# BD0006_1_digit.net
KiCad netlist of a schematic drawn in EAGLE
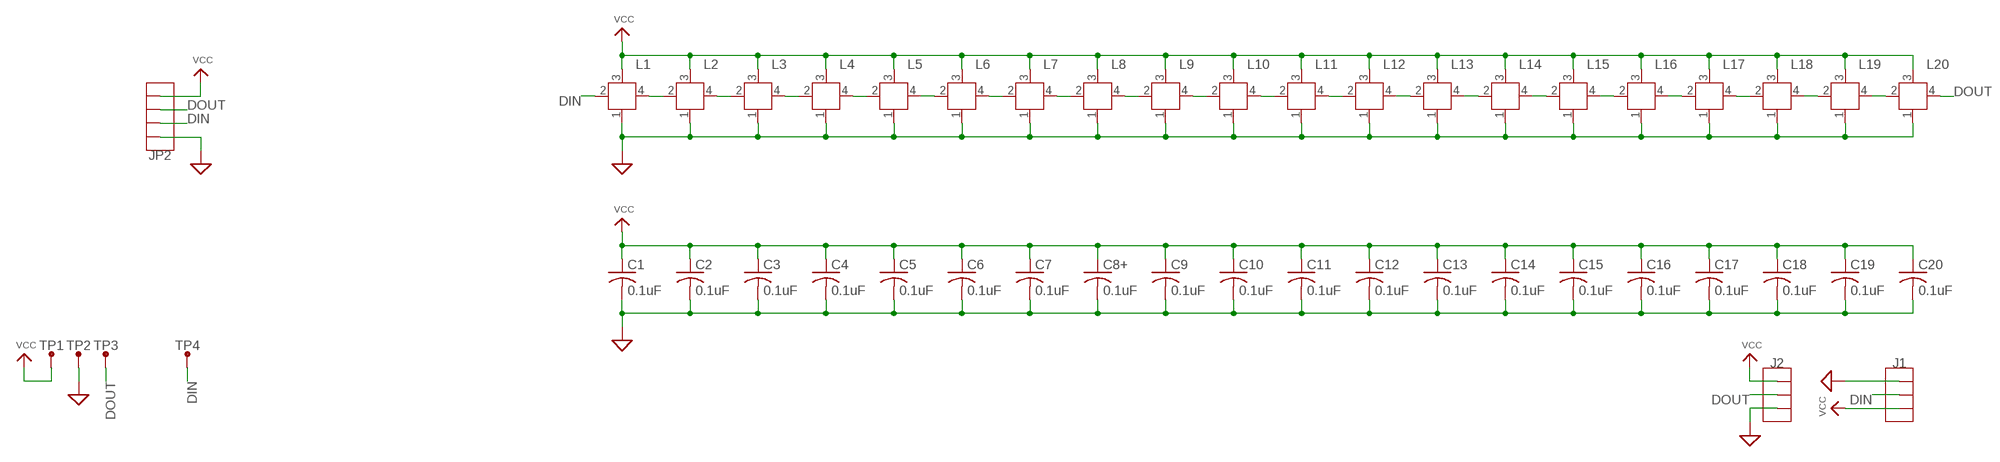
[diagram p0: schematic, sheet 1]

(export (version "E")
  (design (tool "Eeschema 10.0.6"))
  (components
    (comp (ref "C1")
      (value "0.1uF")
      (footprint "eagle-import:C0402")
      (libsource (lib "eagle-import") (part "C-USC0402"))
    )
    (comp (ref "C2")
      (value "0.1uF")
      (footprint "eagle-import:C0402")
      (libsource (lib "eagle-import") (part "C-USC0402"))
    )
    (comp (ref "C3")
      (value "0.1uF")
      (footprint "eagle-import:C0402")
      (libsource (lib "eagle-import") (part "C-USC0402"))
    )
    (comp (ref "C4")
      (value "0.1uF")
      (footprint "eagle-import:C0402")
      (libsource (lib "eagle-import") (part "C-USC0402"))
    )
    (comp (ref "C5")
      (value "0.1uF")
      (footprint "eagle-import:C0402")
      (libsource (lib "eagle-import") (part "C-USC0402"))
    )
    (comp (ref "C6")
      (value "0.1uF")
      (footprint "eagle-import:C0402")
      (libsource (lib "eagle-import") (part "C-USC0402"))
    )
    (comp (ref "C7")
      (value "0.1uF")
      (footprint "eagle-import:C0402")
      (libsource (lib "eagle-import") (part "C-USC0402"))
    )
    (comp (ref "C8+")
      (value "0.1uF")
      (footprint "eagle-import:C0402")
      (libsource (lib "eagle-import") (part "C-USC0402"))
    )
    (comp (ref "C9")
      (value "0.1uF")
      (footprint "eagle-import:C0402")
      (libsource (lib "eagle-import") (part "C-USC0402"))
    )
    (comp (ref "C10")
      (value "0.1uF")
      (footprint "eagle-import:C0402")
      (libsource (lib "eagle-import") (part "C-USC0402"))
    )
    (comp (ref "C11")
      (value "0.1uF")
      (footprint "eagle-import:C0402")
      (libsource (lib "eagle-import") (part "C-USC0402"))
    )
    (comp (ref "C12")
      (value "0.1uF")
      (footprint "eagle-import:C0402")
      (libsource (lib "eagle-import") (part "C-USC0402"))
    )
    (comp (ref "C13")
      (value "0.1uF")
      (footprint "eagle-import:C0402")
      (libsource (lib "eagle-import") (part "C-USC0402"))
    )
    (comp (ref "C14")
      (value "0.1uF")
      (footprint "eagle-import:C0402")
      (libsource (lib "eagle-import") (part "C-USC0402"))
    )
    (comp (ref "C15")
      (value "0.1uF")
      (footprint "eagle-import:C0402")
      (libsource (lib "eagle-import") (part "C-USC0402"))
    )
    (comp (ref "C16")
      (value "0.1uF")
      (footprint "eagle-import:C0402")
      (libsource (lib "eagle-import") (part "C-USC0402"))
    )
    (comp (ref "C17")
      (value "0.1uF")
      (footprint "eagle-import:C0402")
      (libsource (lib "eagle-import") (part "C-USC0402"))
    )
    (comp (ref "C18")
      (value "0.1uF")
      (footprint "eagle-import:C0402")
      (libsource (lib "eagle-import") (part "C-USC0402"))
    )
    (comp (ref "C19")
      (value "0.1uF")
      (footprint "eagle-import:C0402")
      (libsource (lib "eagle-import") (part "C-USC0402"))
    )
    (comp (ref "C20")
      (value "0.1uF")
      (footprint "eagle-import:C0402")
      (libsource (lib "eagle-import") (part "C-USC0402"))
    )
    (comp (ref "J1")
      (value "HEADER_1X3MALE")
      (footprint "eagle-import:M3SMD")
      (libsource (lib "eagle-import") (part "HEADER_1X3MALE"))
    )
    (comp (ref "J2")
      (value "HEADER_1X3FEMALE")
      (footprint "eagle-import:F3SMD")
      (libsource (lib "eagle-import") (part "HEADER_1X3FEMALE"))
    )
    (comp (ref "JP2")
      (value "HEADER_1X4S")
      (footprint "eagle-import:1X04")
      (libsource (lib "eagle-import") (part "HEADER_1X4S"))
    )
    (comp (ref "L1")
      (value "WS2812B")
      (footprint "eagle-import:SK6812")
      (libsource (lib "eagle-import") (part "WS2812B"))
    )
    (comp (ref "L2")
      (value "WS2812B")
      (footprint "eagle-import:SK6812")
      (libsource (lib "eagle-import") (part "WS2812B"))
    )
    (comp (ref "L3")
      (value "WS2812B")
      (footprint "eagle-import:SK6812")
      (libsource (lib "eagle-import") (part "WS2812B"))
    )
    (comp (ref "L4")
      (value "WS2812B")
      (footprint "eagle-import:SK6812")
      (libsource (lib "eagle-import") (part "WS2812B"))
    )
    (comp (ref "L5")
      (value "WS2812B")
      (footprint "eagle-import:SK6812")
      (libsource (lib "eagle-import") (part "WS2812B"))
    )
    (comp (ref "L6")
      (value "WS2812B")
      (footprint "eagle-import:SK6812")
      (libsource (lib "eagle-import") (part "WS2812B"))
    )
    (comp (ref "L7")
      (value "WS2812B")
      (footprint "eagle-import:SK6812")
      (libsource (lib "eagle-import") (part "WS2812B"))
    )
    (comp (ref "L8")
      (value "WS2812B")
      (footprint "eagle-import:SK6812")
      (libsource (lib "eagle-import") (part "WS2812B"))
    )
    (comp (ref "L9")
      (value "WS2812B")
      (footprint "eagle-import:SK6812")
      (libsource (lib "eagle-import") (part "WS2812B"))
    )
    (comp (ref "L10")
      (value "WS2812B")
      (footprint "eagle-import:SK6812")
      (libsource (lib "eagle-import") (part "WS2812B"))
    )
    (comp (ref "L11")
      (value "WS2812B")
      (footprint "eagle-import:SK6812")
      (libsource (lib "eagle-import") (part "WS2812B"))
    )
    (comp (ref "L12")
      (value "WS2812B")
      (footprint "eagle-import:SK6812")
      (libsource (lib "eagle-import") (part "WS2812B"))
    )
    (comp (ref "L13")
      (value "WS2812B")
      (footprint "eagle-import:SK6812")
      (libsource (lib "eagle-import") (part "WS2812B"))
    )
    (comp (ref "L14")
      (value "WS2812B")
      (footprint "eagle-import:SK6812")
      (libsource (lib "eagle-import") (part "WS2812B"))
    )
    (comp (ref "L15")
      (value "WS2812B")
      (footprint "eagle-import:SK6812")
      (libsource (lib "eagle-import") (part "WS2812B"))
    )
    (comp (ref "L16")
      (value "WS2812B")
      (footprint "eagle-import:SK6812")
      (libsource (lib "eagle-import") (part "WS2812B"))
    )
    (comp (ref "L17")
      (value "WS2812B")
      (footprint "eagle-import:SK6812")
      (libsource (lib "eagle-import") (part "WS2812B"))
    )
    (comp (ref "L18")
      (value "WS2812B")
      (footprint "eagle-import:SK6812")
      (libsource (lib "eagle-import") (part "WS2812B"))
    )
    (comp (ref "L19")
      (value "WS2812B")
      (footprint "eagle-import:SK6812")
      (libsource (lib "eagle-import") (part "WS2812B"))
    )
    (comp (ref "L20")
      (value "WS2812B")
      (footprint "eagle-import:SK6812")
      (libsource (lib "eagle-import") (part "WS2812B"))
    )
    (comp (ref "TP1")
      (value "VCC")
      (footprint "eagle-import:TEST_POINT")
      (libsource (lib "eagle-import") (part "TEST_POINT"))
    )
    (comp (ref "TP2")
      (value "GND")
      (footprint "eagle-import:TEST_POINT")
      (libsource (lib "eagle-import") (part "TEST_POINT"))
    )
    (comp (ref "TP3")
      (value "DOUT")
      (footprint "eagle-import:TEST_POINT")
      (libsource (lib "eagle-import") (part "TEST_POINT"))
    )
    (comp (ref "TP4")
      (value "DIN")
      (footprint "eagle-import:TEST_POINT")
      (libsource (lib "eagle-import") (part "TEST_POINT"))
    )
  )
  (nets
    (net (code "1") (name "/DIN") (class "Default")
      (node (ref "J1") (pin "2") (pinfunction "P$2_2") (pintype "bidirectional"))
      (node (ref "JP2") (pin "2") (pinfunction "P$2_2") (pintype "bidirectional"))
      (node (ref "L1") (pin "2") (pinfunction "DIN_2") (pintype "bidirectional"))
      (node (ref "TP4") (pin "P$1") (pinfunction "P$1_P$1") (pintype "input"))
    )
    (net (code "2") (name "/DOUT") (class "Default")
      (node (ref "J2") (pin "2A") (pinfunction "P$2_2A") (pintype "bidirectional"))
      (node (ref "J2") (pin "2B") (pinfunction "P$2_2B") (pintype "bidirectional"))
      (node (ref "JP2") (pin "3") (pinfunction "P$3_3") (pintype "bidirectional"))
      (node (ref "L20") (pin "4") (pinfunction "DOUT_4") (pintype "bidirectional"))
      (node (ref "TP3") (pin "P$1") (pinfunction "P$1_P$1") (pintype "input"))
    )
    (net (code "3") (name "Net-(L1-DOUT)") (class "Default")
      (node (ref "L1") (pin "4") (pinfunction "DOUT_4") (pintype "bidirectional"))
      (node (ref "L2") (pin "2") (pinfunction "DIN_2") (pintype "bidirectional"))
    )
    (net (code "4") (name "Net-(L2-DOUT)") (class "Default")
      (node (ref "L2") (pin "4") (pinfunction "DOUT_4") (pintype "bidirectional"))
      (node (ref "L3") (pin "2") (pinfunction "DIN_2") (pintype "bidirectional"))
    )
    (net (code "5") (name "Net-(L3-DOUT)") (class "Default")
      (node (ref "L3") (pin "4") (pinfunction "DOUT_4") (pintype "bidirectional"))
      (node (ref "L4") (pin "2") (pinfunction "DIN_2") (pintype "bidirectional"))
    )
    (net (code "6") (name "Net-(L4-DOUT)") (class "Default")
      (node (ref "L4") (pin "4") (pinfunction "DOUT_4") (pintype "bidirectional"))
      (node (ref "L5") (pin "2") (pinfunction "DIN_2") (pintype "bidirectional"))
    )
    (net (code "7") (name "Net-(L5-DOUT)") (class "Default")
      (node (ref "L5") (pin "4") (pinfunction "DOUT_4") (pintype "bidirectional"))
      (node (ref "L6") (pin "2") (pinfunction "DIN_2") (pintype "bidirectional"))
    )
    (net (code "8") (name "Net-(L6-DOUT)") (class "Default")
      (node (ref "L6") (pin "4") (pinfunction "DOUT_4") (pintype "bidirectional"))
      (node (ref "L7") (pin "2") (pinfunction "DIN_2") (pintype "bidirectional"))
    )
    (net (code "9") (name "Net-(L7-DOUT)") (class "Default")
      (node (ref "L7") (pin "4") (pinfunction "DOUT_4") (pintype "bidirectional"))
      (node (ref "L8") (pin "2") (pinfunction "DIN_2") (pintype "bidirectional"))
    )
    (net (code "10") (name "Net-(L8-DOUT)") (class "Default")
      (node (ref "L8") (pin "4") (pinfunction "DOUT_4") (pintype "bidirectional"))
      (node (ref "L9") (pin "2") (pinfunction "DIN_2") (pintype "bidirectional"))
    )
    (net (code "11") (name "Net-(L10-DIN)") (class "Default")
      (node (ref "L10") (pin "2") (pinfunction "DIN_2") (pintype "bidirectional"))
      (node (ref "L9") (pin "4") (pinfunction "DOUT_4") (pintype "bidirectional"))
    )
    (net (code "12") (name "Net-(L10-DOUT)") (class "Default")
      (node (ref "L10") (pin "4") (pinfunction "DOUT_4") (pintype "bidirectional"))
      (node (ref "L11") (pin "2") (pinfunction "DIN_2") (pintype "bidirectional"))
    )
    (net (code "13") (name "Net-(L11-DOUT)") (class "Default")
      (node (ref "L11") (pin "4") (pinfunction "DOUT_4") (pintype "bidirectional"))
      (node (ref "L12") (pin "2") (pinfunction "DIN_2") (pintype "bidirectional"))
    )
    (net (code "14") (name "Net-(L12-DOUT)") (class "Default")
      (node (ref "L12") (pin "4") (pinfunction "DOUT_4") (pintype "bidirectional"))
      (node (ref "L13") (pin "2") (pinfunction "DIN_2") (pintype "bidirectional"))
    )
    (net (code "15") (name "Net-(L13-DOUT)") (class "Default")
      (node (ref "L13") (pin "4") (pinfunction "DOUT_4") (pintype "bidirectional"))
      (node (ref "L14") (pin "2") (pinfunction "DIN_2") (pintype "bidirectional"))
    )
    (net (code "16") (name "Net-(L14-DOUT)") (class "Default")
      (node (ref "L14") (pin "4") (pinfunction "DOUT_4") (pintype "bidirectional"))
      (node (ref "L15") (pin "2") (pinfunction "DIN_2") (pintype "bidirectional"))
    )
    (net (code "17") (name "Net-(L15-DOUT)") (class "Default")
      (node (ref "L15") (pin "4") (pinfunction "DOUT_4") (pintype "bidirectional"))
      (node (ref "L16") (pin "2") (pinfunction "DIN_2") (pintype "bidirectional"))
    )
    (net (code "18") (name "Net-(L16-DOUT)") (class "Default")
      (node (ref "L16") (pin "4") (pinfunction "DOUT_4") (pintype "bidirectional"))
      (node (ref "L17") (pin "2") (pinfunction "DIN_2") (pintype "bidirectional"))
    )
    (net (code "19") (name "Net-(L17-DOUT)") (class "Default")
      (node (ref "L17") (pin "4") (pinfunction "DOUT_4") (pintype "bidirectional"))
      (node (ref "L18") (pin "2") (pinfunction "DIN_2") (pintype "bidirectional"))
    )
    (net (code "20") (name "Net-(L18-DOUT)") (class "Default")
      (node (ref "L18") (pin "4") (pinfunction "DOUT_4") (pintype "bidirectional"))
      (node (ref "L19") (pin "2") (pinfunction "DIN_2") (pintype "bidirectional"))
    )
    (net (code "21") (name "Net-(L19-DOUT)") (class "Default")
      (node (ref "L19") (pin "4") (pinfunction "DOUT_4") (pintype "bidirectional"))
      (node (ref "L20") (pin "2") (pinfunction "DIN_2") (pintype "bidirectional"))
    )
    (net (code "22") (name "SUP") (class "Default")
      (node (ref "C1") (pin "2") (pinfunction "2_2") (pintype "passive"))
      (node (ref "C10") (pin "2") (pinfunction "2_2") (pintype "passive"))
      (node (ref "C11") (pin "2") (pinfunction "2_2") (pintype "passive"))
      (node (ref "C12") (pin "2") (pinfunction "2_2") (pintype "passive"))
      (node (ref "C13") (pin "2") (pinfunction "2_2") (pintype "passive"))
      (node (ref "C14") (pin "2") (pinfunction "2_2") (pintype "passive"))
      (node (ref "C15") (pin "2") (pinfunction "2_2") (pintype "passive"))
      (node (ref "C16") (pin "2") (pinfunction "2_2") (pintype "passive"))
      (node (ref "C17") (pin "2") (pinfunction "2_2") (pintype "passive"))
      (node (ref "C18") (pin "2") (pinfunction "2_2") (pintype "passive"))
      (node (ref "C19") (pin "2") (pinfunction "2_2") (pintype "passive"))
      (node (ref "C2") (pin "2") (pinfunction "2_2") (pintype "passive"))
      (node (ref "C20") (pin "2") (pinfunction "2_2") (pintype "passive"))
      (node (ref "C3") (pin "2") (pinfunction "2_2") (pintype "passive"))
      (node (ref "C4") (pin "2") (pinfunction "2_2") (pintype "passive"))
      (node (ref "C5") (pin "2") (pinfunction "2_2") (pintype "passive"))
      (node (ref "C6") (pin "2") (pinfunction "2_2") (pintype "passive"))
      (node (ref "C7") (pin "2") (pinfunction "2_2") (pintype "passive"))
      (node (ref "C8+") (pin "2") (pinfunction "2_2") (pintype "passive"))
      (node (ref "C9") (pin "2") (pinfunction "2_2") (pintype "passive"))
      (node (ref "J1") (pin "1") (pinfunction "P$1_1") (pintype "bidirectional"))
      (node (ref "J2") (pin "3A") (pinfunction "P$3_3A") (pintype "bidirectional"))
      (node (ref "J2") (pin "3B") (pinfunction "P$3_3B") (pintype "bidirectional"))
      (node (ref "JP2") (pin "1") (pinfunction "P$1_1") (pintype "bidirectional"))
      (node (ref "L1") (pin "1") (pinfunction "VSS_1") (pintype "bidirectional"))
      (node (ref "L10") (pin "1") (pinfunction "VSS_1") (pintype "bidirectional"))
      (node (ref "L11") (pin "1") (pinfunction "VSS_1") (pintype "bidirectional"))
      (node (ref "L12") (pin "1") (pinfunction "VSS_1") (pintype "bidirectional"))
      (node (ref "L13") (pin "1") (pinfunction "VSS_1") (pintype "bidirectional"))
      (node (ref "L14") (pin "1") (pinfunction "VSS_1") (pintype "bidirectional"))
      (node (ref "L15") (pin "1") (pinfunction "VSS_1") (pintype "bidirectional"))
      (node (ref "L16") (pin "1") (pinfunction "VSS_1") (pintype "bidirectional"))
      (node (ref "L17") (pin "1") (pinfunction "VSS_1") (pintype "bidirectional"))
      (node (ref "L18") (pin "1") (pinfunction "VSS_1") (pintype "bidirectional"))
      (node (ref "L19") (pin "1") (pinfunction "VSS_1") (pintype "bidirectional"))
      (node (ref "L2") (pin "1") (pinfunction "VSS_1") (pintype "bidirectional"))
      (node (ref "L20") (pin "1") (pinfunction "VSS_1") (pintype "bidirectional"))
      (node (ref "L3") (pin "1") (pinfunction "VSS_1") (pintype "bidirectional"))
      (node (ref "L4") (pin "1") (pinfunction "VSS_1") (pintype "bidirectional"))
      (node (ref "L5") (pin "1") (pinfunction "VSS_1") (pintype "bidirectional"))
      (node (ref "L6") (pin "1") (pinfunction "VSS_1") (pintype "bidirectional"))
      (node (ref "L7") (pin "1") (pinfunction "VSS_1") (pintype "bidirectional"))
      (node (ref "L8") (pin "1") (pinfunction "VSS_1") (pintype "bidirectional"))
      (node (ref "L9") (pin "1") (pinfunction "VSS_1") (pintype "bidirectional"))
      (node (ref "TP2") (pin "P$1") (pinfunction "P$1_P$1") (pintype "input"))
    )
    (net (code "23") (name "VCC") (class "Default")
      (node (ref "C1") (pin "1") (pinfunction "1_1") (pintype "passive"))
      (node (ref "C10") (pin "1") (pinfunction "1_1") (pintype "passive"))
      (node (ref "C11") (pin "1") (pinfunction "1_1") (pintype "passive"))
      (node (ref "C12") (pin "1") (pinfunction "1_1") (pintype "passive"))
      (node (ref "C13") (pin "1") (pinfunction "1_1") (pintype "passive"))
      (node (ref "C14") (pin "1") (pinfunction "1_1") (pintype "passive"))
      (node (ref "C15") (pin "1") (pinfunction "1_1") (pintype "passive"))
      (node (ref "C16") (pin "1") (pinfunction "1_1") (pintype "passive"))
      (node (ref "C17") (pin "1") (pinfunction "1_1") (pintype "passive"))
      (node (ref "C18") (pin "1") (pinfunction "1_1") (pintype "passive"))
      (node (ref "C19") (pin "1") (pinfunction "1_1") (pintype "passive"))
      (node (ref "C2") (pin "1") (pinfunction "1_1") (pintype "passive"))
      (node (ref "C20") (pin "1") (pinfunction "1_1") (pintype "passive"))
      (node (ref "C3") (pin "1") (pinfunction "1_1") (pintype "passive"))
      (node (ref "C4") (pin "1") (pinfunction "1_1") (pintype "passive"))
      (node (ref "C5") (pin "1") (pinfunction "1_1") (pintype "passive"))
      (node (ref "C6") (pin "1") (pinfunction "1_1") (pintype "passive"))
      (node (ref "C7") (pin "1") (pinfunction "1_1") (pintype "passive"))
      (node (ref "C8+") (pin "1") (pinfunction "1_1") (pintype "passive"))
      (node (ref "C9") (pin "1") (pinfunction "1_1") (pintype "passive"))
      (node (ref "J1") (pin "3") (pinfunction "P$3_3") (pintype "bidirectional"))
      (node (ref "J2") (pin "1A") (pinfunction "P$1_1A") (pintype "bidirectional"))
      (node (ref "J2") (pin "1B") (pinfunction "P$1_1B") (pintype "bidirectional"))
      (node (ref "JP2") (pin "4") (pinfunction "P$4_4") (pintype "bidirectional"))
      (node (ref "L1") (pin "3") (pinfunction "VDD_3") (pintype "bidirectional"))
      (node (ref "L10") (pin "3") (pinfunction "VDD_3") (pintype "bidirectional"))
      (node (ref "L11") (pin "3") (pinfunction "VDD_3") (pintype "bidirectional"))
      (node (ref "L12") (pin "3") (pinfunction "VDD_3") (pintype "bidirectional"))
      (node (ref "L13") (pin "3") (pinfunction "VDD_3") (pintype "bidirectional"))
      (node (ref "L14") (pin "3") (pinfunction "VDD_3") (pintype "bidirectional"))
      (node (ref "L15") (pin "3") (pinfunction "VDD_3") (pintype "bidirectional"))
      (node (ref "L16") (pin "3") (pinfunction "VDD_3") (pintype "bidirectional"))
      (node (ref "L17") (pin "3") (pinfunction "VDD_3") (pintype "bidirectional"))
      (node (ref "L18") (pin "3") (pinfunction "VDD_3") (pintype "bidirectional"))
      (node (ref "L19") (pin "3") (pinfunction "VDD_3") (pintype "bidirectional"))
      (node (ref "L2") (pin "3") (pinfunction "VDD_3") (pintype "bidirectional"))
      (node (ref "L20") (pin "3") (pinfunction "VDD_3") (pintype "bidirectional"))
      (node (ref "L3") (pin "3") (pinfunction "VDD_3") (pintype "bidirectional"))
      (node (ref "L4") (pin "3") (pinfunction "VDD_3") (pintype "bidirectional"))
      (node (ref "L5") (pin "3") (pinfunction "VDD_3") (pintype "bidirectional"))
      (node (ref "L6") (pin "3") (pinfunction "VDD_3") (pintype "bidirectional"))
      (node (ref "L7") (pin "3") (pinfunction "VDD_3") (pintype "bidirectional"))
      (node (ref "L8") (pin "3") (pinfunction "VDD_3") (pintype "bidirectional"))
      (node (ref "L9") (pin "3") (pinfunction "VDD_3") (pintype "bidirectional"))
      (node (ref "TP1") (pin "P$1") (pinfunction "P$1_P$1") (pintype "input"))
    )
  )
)
